# 2_0.net
KiCad netlist of a schematic drawn in EasyEDA Pro
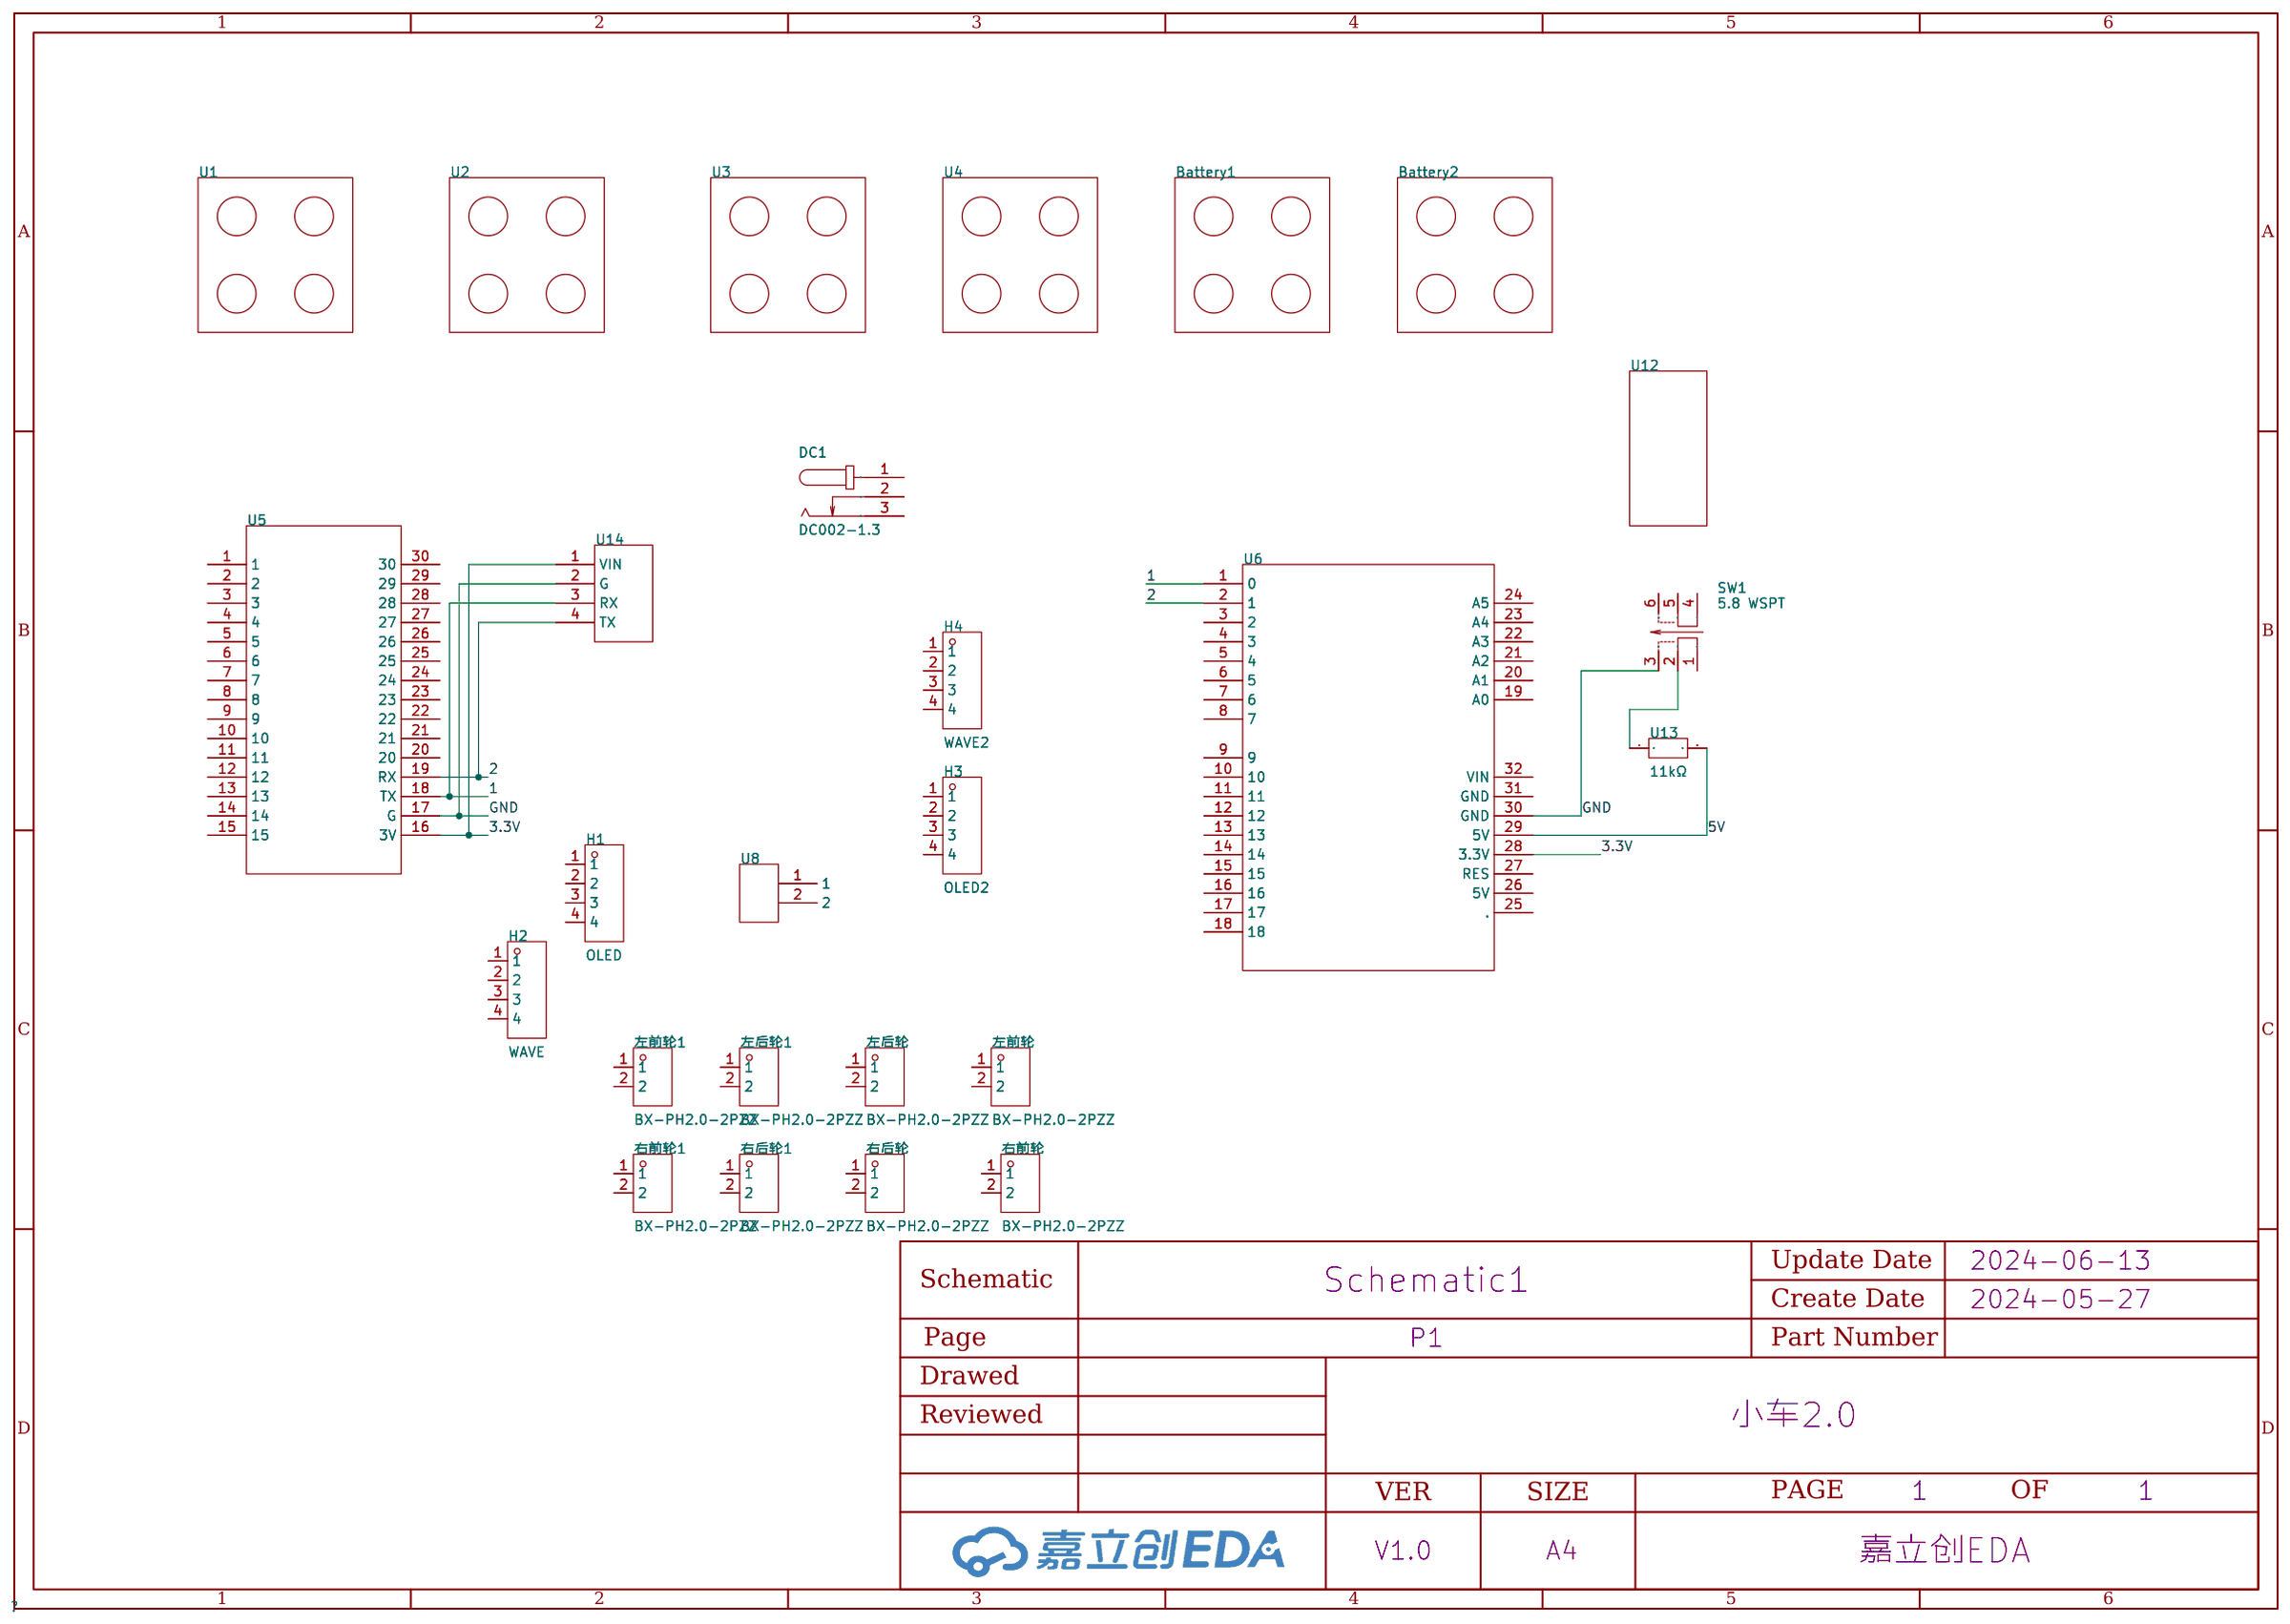
[diagram p0: schematic sheet]

(export (version "E")
  (design (tool "Eeschema 10.0.6"))
  (components
    (comp (ref "Battery1") (value "~") (footprint "easyedapro:车轮") (libsource (lib "easyedapro") (part "车轮")))
    (comp (ref "Battery2") (value "~") (footprint "easyedapro:车轮") (libsource (lib "easyedapro") (part "车轮")))
    (comp (ref "DC1")
      (value "DC002-1.3")
      (footprint "easyedapro:DC-IN-TH_DC002-1.3")
      (description "连接器类型:DC电源插座;安装方式:弯插;触点内径:1.3mm;触点外径:4.2mm;额定电流:500mA;额定电压:30V;工作温度范围:-;")
      (fields (field (name "Manufacturer") "SHOU HAN(首韩)"))
      (libsource (lib "easyedapro") (part "DC002-1.3"))
    )
    (comp (ref "H1")
      (value "OLED")
      (footprint "easyedapro:HDR-TH_4P-P2.54-V-F")
      (description "插孔结构:1x4P;间距:2.54mm;行距:-;安装类型:直插;排数:单排;总孔位数:4P;塑高:-;触头材质:黄铜;触头镀层:-;")
      (fields (field (name "Manufacturer") "XFCN(兴飞)"))
      (libsource (lib "easyedapro") (part "PM254V-11-04-H85"))
    )
    (comp (ref "H2")
      (value "WAVE")
      (footprint "easyedapro:HDR-TH_4P-P2.54-V-F")
      (description "插孔结构:1x4P;间距:2.54mm;行距:-;安装类型:直插;排数:单排;总孔位数:4P;塑高:-;触头材质:黄铜;触头镀层:-;")
      (fields (field (name "Manufacturer") "XFCN(兴飞)"))
      (libsource (lib "easyedapro") (part "PM254V-11-04-H85"))
    )
    (comp (ref "H3")
      (value "OLED2")
      (footprint "easyedapro:HDR-TH_4P-P2.54-V-F")
      (description "插孔结构:1x4P;间距:2.54mm;行距:-;安装类型:直插;排数:单排;总孔位数:4P;塑高:-;触头材质:黄铜;触头镀层:-;")
      (fields (field (name "Manufacturer") "XFCN(兴飞)"))
      (libsource (lib "easyedapro") (part "PM254V-11-04-H85"))
    )
    (comp (ref "H4")
      (value "WAVE2")
      (footprint "easyedapro:HDR-TH_4P-P2.54-V-F")
      (description "插孔结构:1x4P;间距:2.54mm;行距:-;安装类型:直插;排数:单排;总孔位数:4P;塑高:-;触头材质:黄铜;触头镀层:-;")
      (fields (field (name "Manufacturer") "XFCN(兴飞)"))
      (libsource (lib "easyedapro") (part "PM254V-11-04-H85"))
    )
    (comp (ref "SW1")
      (value "5.8 WSPT")
      (footprint "easyedapro:SW-TH_6P-L5.8-W5.8-P2.00-LS4.5-TL_K8-5851E-L1")
      (description "电路结构:双刀双掷;自锁/无锁:无锁;安装方式:直插;触点电流:100mA;额定电压 (AC):-;额定电压 (DC):30V;带灯:不带;作用力:180gf;机械寿命:5千次;")
      (fields (field (name "Manufacturer") "SHOU HAN(首韩)"))
      (libsource (lib "easyedapro") (part "5.8 WSPT"))
    )
    (comp (ref "U1") (value "~") (footprint "easyedapro:车轮") (libsource (lib "easyedapro") (part "车轮")))
    (comp (ref "U2") (value "~") (footprint "easyedapro:车轮") (libsource (lib "easyedapro") (part "车轮")))
    (comp (ref "U3") (value "~") (footprint "easyedapro:车轮") (libsource (lib "easyedapro") (part "车轮")))
    (comp (ref "U4") (value "~") (footprint "easyedapro:车轮") (libsource (lib "easyedapro") (part "车轮")))
    (comp (ref "U5") (value "~") (footprint "easyedapro:蓝牙") (libsource (lib "easyedapro") (part "蓝牙")))
    (comp (ref "U6") (value "~") (footprint "easyedapro:开发板") (libsource (lib "easyedapro") (part "开发板")))
    (comp (ref "U8") (value "~") (footprint "easyedapro:开关") (libsource (lib "easyedapro") (part "开关")))
    (comp (ref "U12") (value "~") (footprint "easyedapro:舵机") (libsource (lib "easyedapro") (part "舵机")))
    (comp (ref "U13")
      (value "11kΩ")
      (footprint "easyedapro:RES-TH_BD2.3-L6.0-P10.00-D0.6")
      (description "电阻类型:金属膜电阻;阻值:11kΩ;精度:±1%;功率:125mW;温度系数:±100ppm/°C;")
      (fields (field (name "Manufacturer Part") "RN55D1102FB14") (field (name "Manufacturer") "VISHAY(威世)"))
      (libsource (lib "easyedapro") (part "RN55D1102FB14"))
    )
    (comp (ref "U14")
      (value "~")
      (footprint "easyedapro:OPENMV")
      (libsource (lib "easyedapro") (part "opnemv"))
    )
    (comp (ref "右前轮")
      (value "BX-PH2.0-2PZZ")
      (footprint "easyedapro:CONN-TH_2P-P2.00_BOSSIE_BX-PH2.0-2PZZ")
      (fields (field (name "Manufacturer") "Bossie(博锡)"))
      (libsource (lib "easyedapro") (part "BX-PH2.0-2PZZ"))
    )
    (comp (ref "右前轮1")
      (value "BX-PH2.0-2PZZ")
      (footprint "easyedapro:CONN-TH_2P-P2.00_BOSSIE_BX-PH2.0-2PZZ")
      (fields (field (name "Manufacturer") "Bossie(博锡)"))
      (libsource (lib "easyedapro") (part "BX-PH2.0-2PZZ"))
    )
    (comp (ref "右后轮")
      (value "BX-PH2.0-2PZZ")
      (footprint "easyedapro:CONN-TH_2P-P2.00_BOSSIE_BX-PH2.0-2PZZ")
      (fields (field (name "Manufacturer") "Bossie(博锡)"))
      (libsource (lib "easyedapro") (part "BX-PH2.0-2PZZ"))
    )
    (comp (ref "右后轮1")
      (value "BX-PH2.0-2PZZ")
      (footprint "easyedapro:CONN-TH_2P-P2.00_BOSSIE_BX-PH2.0-2PZZ")
      (fields (field (name "Manufacturer") "Bossie(博锡)"))
      (libsource (lib "easyedapro") (part "BX-PH2.0-2PZZ"))
    )
    (comp (ref "左前轮")
      (value "BX-PH2.0-2PZZ")
      (footprint "easyedapro:CONN-TH_2P-P2.00_BOSSIE_BX-PH2.0-2PZZ")
      (fields (field (name "Manufacturer") "Bossie(博锡)"))
      (libsource (lib "easyedapro") (part "BX-PH2.0-2PZZ"))
    )
    (comp (ref "左前轮1")
      (value "BX-PH2.0-2PZZ")
      (footprint "easyedapro:CONN-TH_2P-P2.00_BOSSIE_BX-PH2.0-2PZZ")
      (fields (field (name "Manufacturer") "Bossie(博锡)"))
      (libsource (lib "easyedapro") (part "BX-PH2.0-2PZZ"))
    )
    (comp (ref "左后轮")
      (value "BX-PH2.0-2PZZ")
      (footprint "easyedapro:CONN-TH_2P-P2.00_BOSSIE_BX-PH2.0-2PZZ")
      (fields (field (name "Manufacturer") "Bossie(博锡)"))
      (libsource (lib "easyedapro") (part "BX-PH2.0-2PZZ"))
    )
    (comp (ref "左后轮1")
      (value "BX-PH2.0-2PZZ")
      (footprint "easyedapro:CONN-TH_2P-P2.00_BOSSIE_BX-PH2.0-2PZZ")
      (fields (field (name "Manufacturer") "Bossie(博锡)"))
      (libsource (lib "easyedapro") (part "BX-PH2.0-2PZZ"))
    )
  )
  (nets
    (net (code "1") (name "/1") (class "Default")
      (node (ref "U14") (pin "3") (pinfunction "RX_3") (pintype "input"))
      (node (ref "U5") (pin "18") (pinfunction "TX_18") (pintype "input"))
      (node (ref "U6") (pin "1") (pinfunction "0_1") (pintype "input"))
    )
    (net (code "2") (name "/2") (class "Default")
      (node (ref "U14") (pin "4") (pinfunction "TX_4") (pintype "input"))
      (node (ref "U5") (pin "19") (pinfunction "RX_19") (pintype "input"))
      (node (ref "U6") (pin "2") (pinfunction "1_2") (pintype "input"))
    )
    (net (code "3") (name "/3.3V") (class "Default")
      (node (ref "U14") (pin "1") (pinfunction "VIN_1") (pintype "input"))
      (node (ref "U5") (pin "16") (pinfunction "3V_16") (pintype "input"))
      (node (ref "U6") (pin "28") (pinfunction "3.3V_28") (pintype "input"))
    )
    (net (code "4") (name "/5V") (class "Default")
      (node (ref "U13") (pin "2") (pinfunction "2_2") (pintype "unspecified"))
      (node (ref "U6") (pin "29") (pinfunction "5V_29") (pintype "input"))
    )
    (net (code "5") (name "/GND") (class "Default")
      (node (ref "SW1") (pin "3") (pinfunction "3_3") (pintype "unspecified"))
      (node (ref "U14") (pin "2") (pinfunction "G_2") (pintype "input"))
      (node (ref "U5") (pin "17") (pinfunction "G_17") (pintype "input"))
      (node (ref "U6") (pin "30") (pinfunction "GND_30") (pintype "input"))
    )
    (net (code "6") (name "Net-(SW1-Pad2)") (class "Default")
      (node (ref "SW1") (pin "2") (pinfunction "2_2") (pintype "unspecified"))
      (node (ref "U13") (pin "1") (pinfunction "1_1") (pintype "unspecified"))
    )
    (net (code "7") (name "unconnected-(DC1-Pad1)") (class "Default")
      (node (ref "DC1") (pin "1") (pinfunction "1_1") (pintype "input"))
    )
    (net (code "8") (name "unconnected-(DC1-Pad2)") (class "Default")
      (node (ref "DC1") (pin "2") (pinfunction "2_2") (pintype "input"))
    )
    (net (code "9") (name "unconnected-(DC1-Pad3)") (class "Default")
      (node (ref "DC1") (pin "3") (pinfunction "3_3") (pintype "input"))
    )
    (net (code "10") (name "unconnected-(H1-Pad1)") (class "Default")
      (node (ref "H1") (pin "1") (pinfunction "1_1") (pintype "unspecified"))
    )
    (net (code "11") (name "unconnected-(H1-Pad2)") (class "Default")
      (node (ref "H1") (pin "2") (pinfunction "2_2") (pintype "unspecified"))
    )
    (net (code "12") (name "unconnected-(H1-Pad3)") (class "Default")
      (node (ref "H1") (pin "3") (pinfunction "3_3") (pintype "unspecified"))
    )
    (net (code "13") (name "unconnected-(H1-Pad4)") (class "Default")
      (node (ref "H1") (pin "4") (pinfunction "4_4") (pintype "unspecified"))
    )
    (net (code "14") (name "unconnected-(H2-Pad1)") (class "Default")
      (node (ref "H2") (pin "1") (pinfunction "1_1") (pintype "unspecified"))
    )
    (net (code "15") (name "unconnected-(H2-Pad2)") (class "Default")
      (node (ref "H2") (pin "2") (pinfunction "2_2") (pintype "unspecified"))
    )
    (net (code "16") (name "unconnected-(H2-Pad3)") (class "Default")
      (node (ref "H2") (pin "3") (pinfunction "3_3") (pintype "unspecified"))
    )
    (net (code "17") (name "unconnected-(H2-Pad4)") (class "Default")
      (node (ref "H2") (pin "4") (pinfunction "4_4") (pintype "unspecified"))
    )
    (net (code "18") (name "unconnected-(H3-Pad1)") (class "Default")
      (node (ref "H3") (pin "1") (pinfunction "1_1") (pintype "unspecified"))
    )
    (net (code "19") (name "unconnected-(H3-Pad2)") (class "Default")
      (node (ref "H3") (pin "2") (pinfunction "2_2") (pintype "unspecified"))
    )
    (net (code "20") (name "unconnected-(H3-Pad3)") (class "Default")
      (node (ref "H3") (pin "3") (pinfunction "3_3") (pintype "unspecified"))
    )
    (net (code "21") (name "unconnected-(H3-Pad4)") (class "Default")
      (node (ref "H3") (pin "4") (pinfunction "4_4") (pintype "unspecified"))
    )
    (net (code "22") (name "unconnected-(H4-Pad1)") (class "Default")
      (node (ref "H4") (pin "1") (pinfunction "1_1") (pintype "unspecified"))
    )
    (net (code "23") (name "unconnected-(H4-Pad2)") (class "Default")
      (node (ref "H4") (pin "2") (pinfunction "2_2") (pintype "unspecified"))
    )
    (net (code "24") (name "unconnected-(H4-Pad3)") (class "Default")
      (node (ref "H4") (pin "3") (pinfunction "3_3") (pintype "unspecified"))
    )
    (net (code "25") (name "unconnected-(H4-Pad4)") (class "Default")
      (node (ref "H4") (pin "4") (pinfunction "4_4") (pintype "unspecified"))
    )
    (net (code "26") (name "unconnected-(SW1-Pad1)") (class "Default")
      (node (ref "SW1") (pin "1") (pinfunction "1_1") (pintype "unspecified"))
    )
    (net (code "27") (name "unconnected-(SW1-Pad4)") (class "Default")
      (node (ref "SW1") (pin "4") (pinfunction "4_4") (pintype "unspecified"))
    )
    (net (code "28") (name "unconnected-(SW1-Pad5)") (class "Default")
      (node (ref "SW1") (pin "5") (pinfunction "5_5") (pintype "unspecified"))
    )
    (net (code "29") (name "unconnected-(SW1-Pad6)") (class "Default")
      (node (ref "SW1") (pin "6") (pinfunction "6_6") (pintype "unspecified"))
    )
    (net (code "30") (name "unconnected-(U5-Pad1)") (class "Default")
      (node (ref "U5") (pin "1") (pinfunction "1_1") (pintype "input"))
    )
    (net (code "31") (name "unconnected-(U5-Pad2)") (class "Default")
      (node (ref "U5") (pin "2") (pinfunction "2_2") (pintype "input"))
    )
    (net (code "32") (name "unconnected-(U5-Pad3)") (class "Default")
      (node (ref "U5") (pin "3") (pinfunction "3_3") (pintype "input"))
    )
    (net (code "33") (name "unconnected-(U5-Pad4)") (class "Default")
      (node (ref "U5") (pin "4") (pinfunction "4_4") (pintype "input"))
    )
    (net (code "34") (name "unconnected-(U5-Pad5)") (class "Default")
      (node (ref "U5") (pin "5") (pinfunction "5_5") (pintype "input"))
    )
    (net (code "35") (name "unconnected-(U5-Pad6)") (class "Default")
      (node (ref "U5") (pin "6") (pinfunction "6_6") (pintype "input"))
    )
    (net (code "36") (name "unconnected-(U5-Pad7)") (class "Default")
      (node (ref "U5") (pin "7") (pinfunction "7_7") (pintype "input"))
    )
    (net (code "37") (name "unconnected-(U5-Pad8)") (class "Default")
      (node (ref "U5") (pin "8") (pinfunction "8_8") (pintype "input"))
    )
    (net (code "38") (name "unconnected-(U5-Pad9)") (class "Default")
      (node (ref "U5") (pin "9") (pinfunction "9_9") (pintype "input"))
    )
    (net (code "39") (name "unconnected-(U5-Pad10)") (class "Default")
      (node (ref "U5") (pin "10") (pinfunction "10_10") (pintype "input"))
    )
    (net (code "40") (name "unconnected-(U5-Pad11)") (class "Default")
      (node (ref "U5") (pin "11") (pinfunction "11_11") (pintype "input"))
    )
    (net (code "41") (name "unconnected-(U5-Pad12)") (class "Default")
      (node (ref "U5") (pin "12") (pinfunction "12_12") (pintype "input"))
    )
    (net (code "42") (name "unconnected-(U5-Pad13)") (class "Default")
      (node (ref "U5") (pin "13") (pinfunction "13_13") (pintype "input"))
    )
    (net (code "43") (name "unconnected-(U5-Pad14)") (class "Default")
      (node (ref "U5") (pin "14") (pinfunction "14_14") (pintype "input"))
    )
    (net (code "44") (name "unconnected-(U5-Pad15)") (class "Default")
      (node (ref "U5") (pin "15") (pinfunction "15_15") (pintype "input"))
    )
    (net (code "45") (name "unconnected-(U5-Pad20)") (class "Default")
      (node (ref "U5") (pin "20") (pinfunction "20_20") (pintype "input"))
    )
    (net (code "46") (name "unconnected-(U5-Pad21)") (class "Default")
      (node (ref "U5") (pin "21") (pinfunction "21_21") (pintype "input"))
    )
    (net (code "47") (name "unconnected-(U5-Pad22)") (class "Default")
      (node (ref "U5") (pin "22") (pinfunction "22_22") (pintype "input"))
    )
    (net (code "48") (name "unconnected-(U5-Pad23)") (class "Default")
      (node (ref "U5") (pin "23") (pinfunction "23_23") (pintype "input"))
    )
    (net (code "49") (name "unconnected-(U5-Pad24)") (class "Default")
      (node (ref "U5") (pin "24") (pinfunction "24_24") (pintype "input"))
    )
    (net (code "50") (name "unconnected-(U5-Pad25)") (class "Default")
      (node (ref "U5") (pin "25") (pinfunction "25_25") (pintype "input"))
    )
    (net (code "51") (name "unconnected-(U5-Pad26)") (class "Default")
      (node (ref "U5") (pin "26") (pinfunction "26_26") (pintype "input"))
    )
    (net (code "52") (name "unconnected-(U5-Pad27)") (class "Default")
      (node (ref "U5") (pin "27") (pinfunction "27_27") (pintype "input"))
    )
    (net (code "53") (name "unconnected-(U5-Pad28)") (class "Default")
      (node (ref "U5") (pin "28") (pinfunction "28_28") (pintype "input"))
    )
    (net (code "54") (name "unconnected-(U5-Pad29)") (class "Default")
      (node (ref "U5") (pin "29") (pinfunction "29_29") (pintype "input"))
    )
    (net (code "55") (name "unconnected-(U5-Pad30)") (class "Default")
      (node (ref "U5") (pin "30") (pinfunction "30_30") (pintype "input"))
    )
    (net (code "56") (name "unconnected-(U6-.-Pad25)") (class "Default")
      (node (ref "U6") (pin "25") (pinfunction "._25") (pintype "input"))
    )
    (net (code "57") (name "unconnected-(U6-2-Pad3)") (class "Default")
      (node (ref "U6") (pin "3") (pinfunction "2_3") (pintype "input"))
    )
    (net (code "58") (name "unconnected-(U6-3-Pad4)") (class "Default")
      (node (ref "U6") (pin "4") (pinfunction "3_4") (pintype "input"))
    )
    (net (code "59") (name "unconnected-(U6-4-Pad5)") (class "Default")
      (node (ref "U6") (pin "5") (pinfunction "4_5") (pintype "input"))
    )
    (net (code "60") (name "unconnected-(U6-5-Pad6)") (class "Default")
      (node (ref "U6") (pin "6") (pinfunction "5_6") (pintype "input"))
    )
    (net (code "61") (name "unconnected-(U6-5V-Pad26)") (class "Default")
      (node (ref "U6") (pin "26") (pinfunction "5V_26") (pintype "input"))
    )
    (net (code "62") (name "unconnected-(U6-6-Pad7)") (class "Default")
      (node (ref "U6") (pin "7") (pinfunction "6_7") (pintype "input"))
    )
    (net (code "63") (name "unconnected-(U6-7-Pad8)") (class "Default")
      (node (ref "U6") (pin "8") (pinfunction "7_8") (pintype "input"))
    )
    (net (code "64") (name "unconnected-(U6-A0-Pad19)") (class "Default")
      (node (ref "U6") (pin "19") (pinfunction "A0_19") (pintype "input"))
    )
    (net (code "65") (name "unconnected-(U6-A1-Pad20)") (class "Default")
      (node (ref "U6") (pin "20") (pinfunction "A1_20") (pintype "input"))
    )
    (net (code "66") (name "unconnected-(U6-A2-Pad21)") (class "Default")
      (node (ref "U6") (pin "21") (pinfunction "A2_21") (pintype "input"))
    )
    (net (code "67") (name "unconnected-(U6-A3-Pad22)") (class "Default")
      (node (ref "U6") (pin "22") (pinfunction "A3_22") (pintype "input"))
    )
    (net (code "68") (name "unconnected-(U6-A4-Pad23)") (class "Default")
      (node (ref "U6") (pin "23") (pinfunction "A4_23") (pintype "input"))
    )
    (net (code "69") (name "unconnected-(U6-A5-Pad24)") (class "Default")
      (node (ref "U6") (pin "24") (pinfunction "A5_24") (pintype "input"))
    )
    (net (code "70") (name "unconnected-(U6-GND-Pad31)") (class "Default")
      (node (ref "U6") (pin "31") (pinfunction "GND_31") (pintype "input"))
    )
    (net (code "71") (name "unconnected-(U6-Pad9)") (class "Default")
      (node (ref "U6") (pin "9") (pinfunction "9_9") (pintype "input"))
    )
    (net (code "72") (name "unconnected-(U6-Pad10)") (class "Default")
      (node (ref "U6") (pin "10") (pinfunction "10_10") (pintype "input"))
    )
    (net (code "73") (name "unconnected-(U6-Pad11)") (class "Default")
      (node (ref "U6") (pin "11") (pinfunction "11_11") (pintype "input"))
    )
    (net (code "74") (name "unconnected-(U6-Pad12)") (class "Default")
      (node (ref "U6") (pin "12") (pinfunction "12_12") (pintype "input"))
    )
    (net (code "75") (name "unconnected-(U6-Pad13)") (class "Default")
      (node (ref "U6") (pin "13") (pinfunction "13_13") (pintype "input"))
    )
    (net (code "76") (name "unconnected-(U6-Pad14)") (class "Default")
      (node (ref "U6") (pin "14") (pinfunction "14_14") (pintype "input"))
    )
    (net (code "77") (name "unconnected-(U6-Pad15)") (class "Default")
      (node (ref "U6") (pin "15") (pinfunction "15_15") (pintype "input"))
    )
    (net (code "78") (name "unconnected-(U6-Pad16)") (class "Default")
      (node (ref "U6") (pin "16") (pinfunction "16_16") (pintype "input"))
    )
    (net (code "79") (name "unconnected-(U6-Pad17)") (class "Default")
      (node (ref "U6") (pin "17") (pinfunction "17_17") (pintype "input"))
    )
    (net (code "80") (name "unconnected-(U6-Pad18)") (class "Default")
      (node (ref "U6") (pin "18") (pinfunction "18_18") (pintype "input"))
    )
    (net (code "81") (name "unconnected-(U6-RES-Pad27)") (class "Default")
      (node (ref "U6") (pin "27") (pinfunction "RES_27") (pintype "input"))
    )
    (net (code "82") (name "unconnected-(U6-VIN-Pad32)") (class "Default")
      (node (ref "U6") (pin "32") (pinfunction "VIN_32") (pintype "input"))
    )
    (net (code "83") (name "unconnected-(U8-Pad1)") (class "Default")
      (node (ref "U8") (pin "1") (pinfunction "1_1") (pintype "input"))
    )
    (net (code "84") (name "unconnected-(U8-Pad2)") (class "Default")
      (node (ref "U8") (pin "2") (pinfunction "2_2") (pintype "input"))
    )
    (net (code "85") (name "unconnected-(右前轮-Pad1)") (class "Default")
      (node (ref "右前轮") (pin "1") (pinfunction "1_1") (pintype "unspecified"))
    )
    (net (code "86") (name "unconnected-(右前轮-Pad2)") (class "Default")
      (node (ref "右前轮") (pin "2") (pinfunction "2_2") (pintype "unspecified"))
    )
    (net (code "87") (name "unconnected-(右前轮1-Pad1)") (class "Default")
      (node (ref "右前轮1") (pin "1") (pinfunction "1_1") (pintype "unspecified"))
    )
    (net (code "88") (name "unconnected-(右前轮1-Pad2)") (class "Default")
      (node (ref "右前轮1") (pin "2") (pinfunction "2_2") (pintype "unspecified"))
    )
    (net (code "89") (name "unconnected-(右后轮-Pad1)") (class "Default")
      (node (ref "右后轮") (pin "1") (pinfunction "1_1") (pintype "unspecified"))
    )
    (net (code "90") (name "unconnected-(右后轮-Pad2)") (class "Default")
      (node (ref "右后轮") (pin "2") (pinfunction "2_2") (pintype "unspecified"))
    )
    (net (code "91") (name "unconnected-(右后轮1-Pad1)") (class "Default")
      (node (ref "右后轮1") (pin "1") (pinfunction "1_1") (pintype "unspecified"))
    )
    (net (code "92") (name "unconnected-(右后轮1-Pad2)") (class "Default")
      (node (ref "右后轮1") (pin "2") (pinfunction "2_2") (pintype "unspecified"))
    )
    (net (code "93") (name "unconnected-(左前轮-Pad1)") (class "Default")
      (node (ref "左前轮") (pin "1") (pinfunction "1_1") (pintype "unspecified"))
    )
    (net (code "94") (name "unconnected-(左前轮-Pad2)") (class "Default")
      (node (ref "左前轮") (pin "2") (pinfunction "2_2") (pintype "unspecified"))
    )
    (net (code "95") (name "unconnected-(左前轮1-Pad1)") (class "Default")
      (node (ref "左前轮1") (pin "1") (pinfunction "1_1") (pintype "unspecified"))
    )
    (net (code "96") (name "unconnected-(左前轮1-Pad2)") (class "Default")
      (node (ref "左前轮1") (pin "2") (pinfunction "2_2") (pintype "unspecified"))
    )
    (net (code "97") (name "unconnected-(左后轮-Pad1)") (class "Default")
      (node (ref "左后轮") (pin "1") (pinfunction "1_1") (pintype "unspecified"))
    )
    (net (code "98") (name "unconnected-(左后轮-Pad2)") (class "Default")
      (node (ref "左后轮") (pin "2") (pinfunction "2_2") (pintype "unspecified"))
    )
    (net (code "99") (name "unconnected-(左后轮1-Pad1)") (class "Default")
      (node (ref "左后轮1") (pin "1") (pinfunction "1_1") (pintype "unspecified"))
    )
    (net (code "100") (name "unconnected-(左后轮1-Pad2)") (class "Default")
      (node (ref "左后轮1") (pin "2") (pinfunction "2_2") (pintype "unspecified"))
    )
  )
)
